# HW1_Micro2.net
KiCad netlist of a schematic drawn in EAGLE
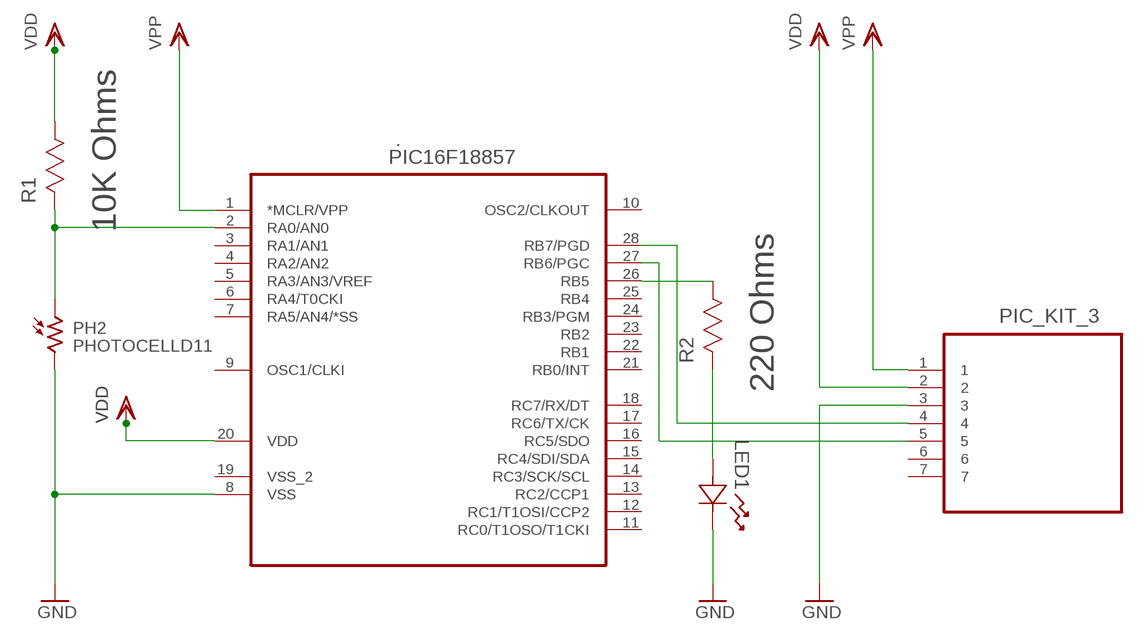
[diagram p0: schematic, sheet 1]

(export (version "E")
  (design (tool "Eeschema 10.0.6"))
  (components
    (comp (ref ".")
      (value "PIC16F18857")
      (footprint "eagle-import:DIP254P724X406-28")
      (fields (field (name "MPN") "PIC16LF76-I/SP"))
      (libsource (lib "eagle-import") (part "PIC16LF76-I/SP"))
    )
    (comp (ref "LED1")
      (value "CMD17-21VYC_TR8")
      (footprint "eagle-import:LED_CMD17-21VYC_TR8")
      (libsource (lib "eagle-import") (part "CMD17-21VYC_TR8"))
    )
    (comp (ref "PH2")
      (value "PHOTOCELLD11")
      (footprint "eagle-import:D11XX_H")
      (libsource (lib "eagle-import") (part "PHOTOCELLD11"))
    )
    (comp (ref "PIC_KIT_3")
      (value "TLW-107-06-T-S")
      (footprint "eagle-import:SAMTEC_TLW-107-06-T-S")
      (libsource (lib "eagle-import") (part "TLW-107-06-T-S"))
    )
    (comp (ref "R1")
      (value "10K Ohms")
      (footprint "eagle-import:RESC1608X60N")
      (fields (field (name "MPN") "CRCW060312K4FKEA") (field (name "TOLERANCE") "± 1.0 %"))
      (libsource (lib "eagle-import") (part "CRCW060312K4FKEA"))
    )
    (comp (ref "R2")
      (value "220 Ohms")
      (footprint "eagle-import:RESC1608X60N")
      (fields (field (name "MPN") "CRCW060312K4FKEA") (field (name "TOLERANCE") "± 1.0 %"))
      (libsource (lib "eagle-import") (part "CRCW060312K4FKEA"))
    )
  )
  (nets
    (net (code "1") (name "GND") (class "Default")
      (node (ref ".") (pin "8") (pinfunction "VSS_8") (pintype "passive"))
      (node (ref "LED1") (pin "2") (pinfunction "2_2") (pintype "passive"))
      (node (ref "PH2") (pin "2") (pinfunction "2_2") (pintype "passive"))
      (node (ref "PIC_KIT_3") (pin "3") (pinfunction "3_3") (pintype "passive"))
    )
    (net (code "2") (name "Net-(.-RA0{slash}AN0)") (class "Default")
      (node (ref ".") (pin "2") (pinfunction "RA0/AN0_2") (pintype "bidirectional"))
      (node (ref "PH2") (pin "1") (pinfunction "1_1") (pintype "passive"))
      (node (ref "R1") (pin "2") (pinfunction "2_2") (pintype "passive"))
    )
    (net (code "3") (name "Net-(.-RB5)") (class "Default")
      (node (ref ".") (pin "26") (pinfunction "RB5_26") (pintype "bidirectional"))
      (node (ref "R2") (pin "1") (pinfunction "1_1") (pintype "passive"))
    )
    (net (code "4") (name "Net-(.-RB6{slash}PGC)") (class "Default")
      (node (ref ".") (pin "27") (pinfunction "RB6/PGC_27") (pintype "bidirectional"))
      (node (ref "PIC_KIT_3") (pin "5") (pinfunction "5_5") (pintype "passive"))
    )
    (net (code "5") (name "Net-(.-RB7{slash}PGD)") (class "Default")
      (node (ref ".") (pin "28") (pinfunction "RB7/PGD_28") (pintype "bidirectional"))
      (node (ref "PIC_KIT_3") (pin "4") (pinfunction "4_4") (pintype "passive"))
    )
    (net (code "6") (name "Net-(LED1-Pad1)") (class "Default")
      (node (ref "LED1") (pin "1") (pinfunction "1_1") (pintype "passive"))
      (node (ref "R2") (pin "2") (pinfunction "2_2") (pintype "passive"))
    )
    (net (code "7") (name "VDD") (class "Default")
      (node (ref ".") (pin "1") (pinfunction "*MCLR/VPP_1") (pintype "input"))
      (node (ref ".") (pin "20") (pinfunction "VDD_20") (pintype "power_in"))
      (node (ref "PIC_KIT_3") (pin "1") (pinfunction "1_1") (pintype "passive"))
      (node (ref "PIC_KIT_3") (pin "2") (pinfunction "2_2") (pintype "passive"))
      (node (ref "R1") (pin "1") (pinfunction "1_1") (pintype "passive"))
    )
    (net (code "8") (name "unconnected-(.-OSC1{slash}CLKI-Pad9)") (class "Default")
      (node (ref ".") (pin "9") (pinfunction "OSC1/CLKI_9") (pintype "input"))
    )
    (net (code "9") (name "unconnected-(.-OSC2{slash}CLKOUT-Pad10)") (class "Default")
      (node (ref ".") (pin "10") (pinfunction "OSC2/CLKOUT_10") (pintype "output"))
    )
    (net (code "10") (name "unconnected-(.-RA1{slash}AN1-Pad3)") (class "Default")
      (node (ref ".") (pin "3") (pinfunction "RA1/AN1_3") (pintype "bidirectional"))
    )
    (net (code "11") (name "unconnected-(.-RA2{slash}AN2-Pad4)") (class "Default")
      (node (ref ".") (pin "4") (pinfunction "RA2/AN2_4") (pintype "bidirectional"))
    )
    (net (code "12") (name "unconnected-(.-RA3{slash}AN3{slash}VREF-Pad5)") (class "Default")
      (node (ref ".") (pin "5") (pinfunction "RA3/AN3/VREF_5") (pintype "bidirectional"))
    )
    (net (code "13") (name "unconnected-(.-RA4{slash}T0CKI-Pad6)") (class "Default")
      (node (ref ".") (pin "6") (pinfunction "RA4/T0CKI_6") (pintype "bidirectional"))
    )
    (net (code "14") (name "unconnected-(.-RA5{slash}AN4{slash}*SS-Pad7)") (class "Default")
      (node (ref ".") (pin "7") (pinfunction "RA5/AN4/*SS_7") (pintype "bidirectional"))
    )
    (net (code "15") (name "unconnected-(.-RB0{slash}INT-Pad21)") (class "Default")
      (node (ref ".") (pin "21") (pinfunction "RB0/INT_21") (pintype "bidirectional"))
    )
    (net (code "16") (name "unconnected-(.-RB1-Pad22)") (class "Default")
      (node (ref ".") (pin "22") (pinfunction "RB1_22") (pintype "bidirectional"))
    )
    (net (code "17") (name "unconnected-(.-RB2-Pad23)") (class "Default")
      (node (ref ".") (pin "23") (pinfunction "RB2_23") (pintype "bidirectional"))
    )
    (net (code "18") (name "unconnected-(.-RB3{slash}PGM-Pad24)") (class "Default")
      (node (ref ".") (pin "24") (pinfunction "RB3/PGM_24") (pintype "bidirectional"))
    )
    (net (code "19") (name "unconnected-(.-RB4-Pad25)") (class "Default")
      (node (ref ".") (pin "25") (pinfunction "RB4_25") (pintype "bidirectional"))
    )
    (net (code "20") (name "unconnected-(.-RC0{slash}T1OSO{slash}T1CKI-Pad11)") (class "Default")
      (node (ref ".") (pin "11") (pinfunction "RC0/T1OSO/T1CKI_11") (pintype "bidirectional"))
    )
    (net (code "21") (name "unconnected-(.-RC1{slash}T1OSI{slash}CCP2-Pad12)") (class "Default")
      (node (ref ".") (pin "12") (pinfunction "RC1/T1OSI/CCP2_12") (pintype "bidirectional"))
    )
    (net (code "22") (name "unconnected-(.-RC2{slash}CCP1-Pad13)") (class "Default")
      (node (ref ".") (pin "13") (pinfunction "RC2/CCP1_13") (pintype "bidirectional"))
    )
    (net (code "23") (name "unconnected-(.-RC3{slash}SCK{slash}SCL-Pad14)") (class "Default")
      (node (ref ".") (pin "14") (pinfunction "RC3/SCK/SCL_14") (pintype "bidirectional"))
    )
    (net (code "24") (name "unconnected-(.-RC4{slash}SDI{slash}SDA-Pad15)") (class "Default")
      (node (ref ".") (pin "15") (pinfunction "RC4/SDI/SDA_15") (pintype "bidirectional"))
    )
    (net (code "25") (name "unconnected-(.-RC5{slash}SDO-Pad16)") (class "Default")
      (node (ref ".") (pin "16") (pinfunction "RC5/SDO_16") (pintype "bidirectional"))
    )
    (net (code "26") (name "unconnected-(.-RC6{slash}TX{slash}CK-Pad17)") (class "Default")
      (node (ref ".") (pin "17") (pinfunction "RC6/TX/CK_17") (pintype "bidirectional"))
    )
    (net (code "27") (name "unconnected-(.-RC7{slash}RX{slash}DT-Pad18)") (class "Default")
      (node (ref ".") (pin "18") (pinfunction "RC7/RX/DT_18") (pintype "bidirectional"))
    )
    (net (code "28") (name "unconnected-(.-VSS_2-Pad19)") (class "Default")
      (node (ref ".") (pin "19") (pinfunction "VSS_2_19") (pintype "passive"))
    )
    (net (code "29") (name "unconnected-(PIC_KIT_3-Pad6)") (class "Default")
      (node (ref "PIC_KIT_3") (pin "6") (pinfunction "6_6") (pintype "passive"))
    )
    (net (code "30") (name "unconnected-(PIC_KIT_3-Pad7)") (class "Default")
      (node (ref "PIC_KIT_3") (pin "7") (pinfunction "7_7") (pintype "passive"))
    )
  )
)
